# POWER_GEN.net
KiCad netlist of a schematic drawn in Altium Designer
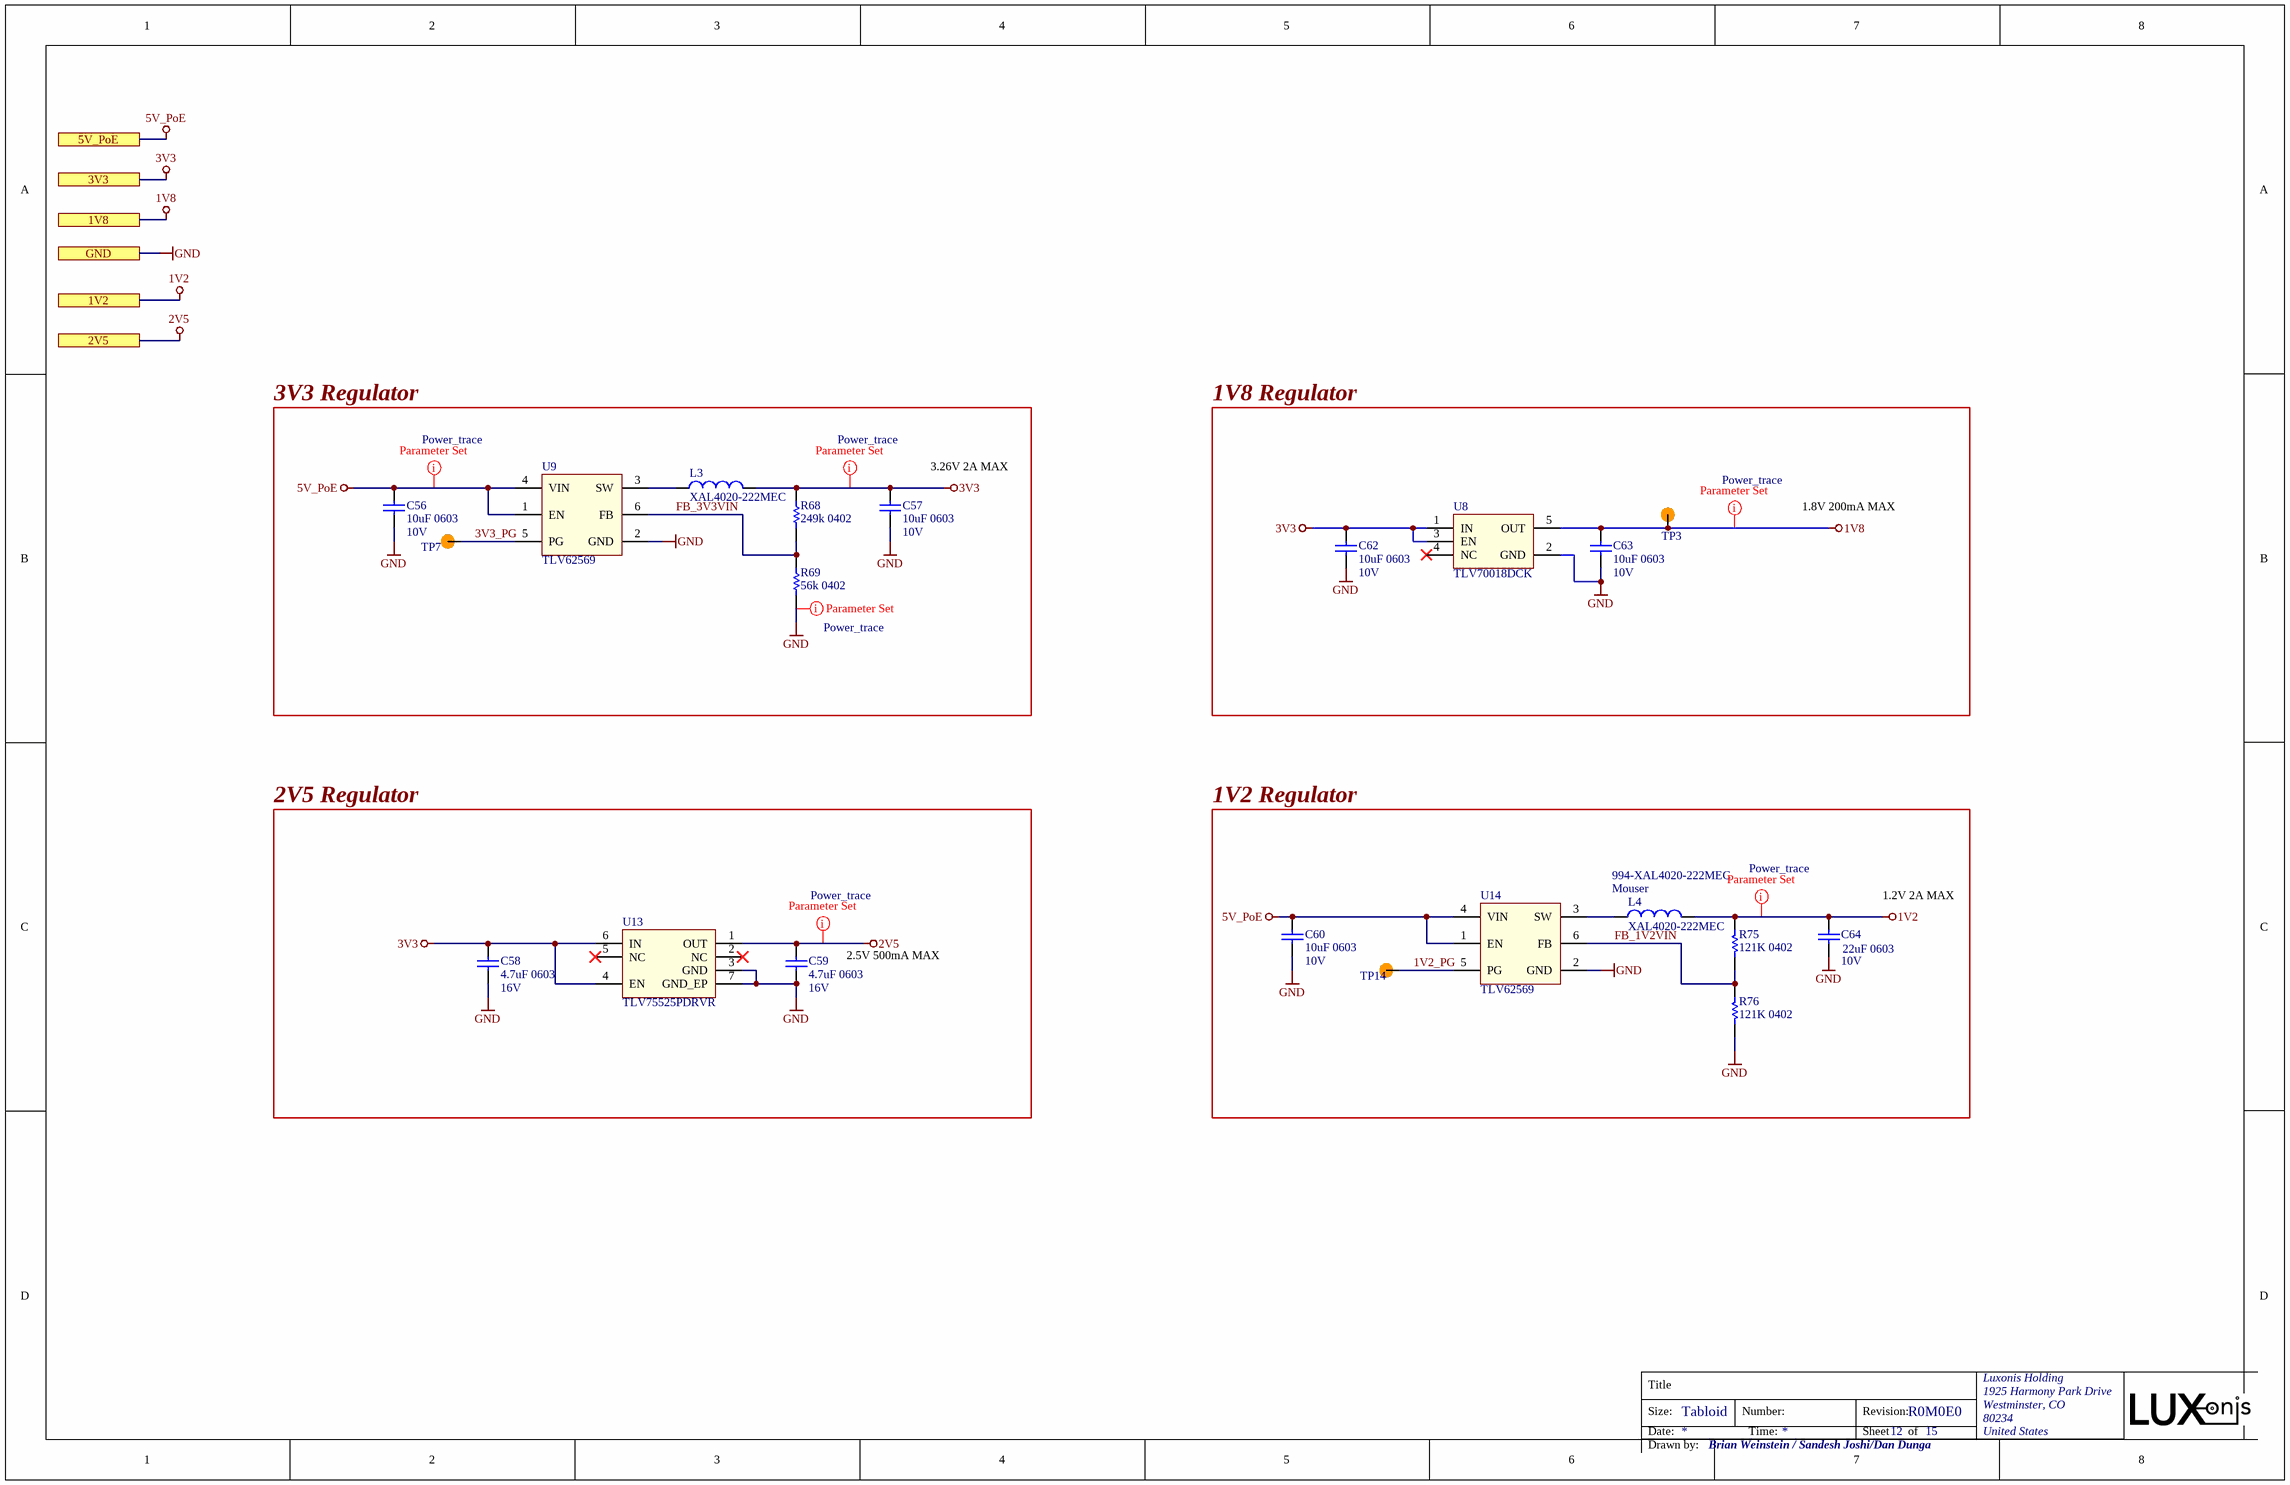
[diagram p0: POWER_GEN.SchDoc]

(export (version "E")
  (design (tool "Eeschema 10.0.6"))
  (components
    (comp (ref "C56")
      (value "10uF 0603")
      (footprint "CAP_Altium_Vault_Generic:CAPC0603(1608)100_N")
      (description "CAP CER 10UF 10V X5R 0603 20%")
      (fields (field (name "TOLERANCE") "20%") (field (name "VOLTAGE RATING") "10V"))
      (libsource (lib "OSHW_LuxonisMaster_20201223") (part "GRM188R61A106ME69D"))
    )
    (comp (ref "C57")
      (value "10uF 0603")
      (footprint "CAP_Altium_Vault_Generic:CAPC0603(1608)100_N")
      (description "CAP CER 10UF 10V X5R 0603 20%")
      (fields (field (name "TOLERANCE") "20%") (field (name "VOLTAGE RATING") "10V"))
      (libsource (lib "OSHW_LuxonisMaster_20201223") (part "GRM188R61A106ME69D"))
    )
    (comp (ref "C58")
      (value "4.7uF 0603")
      (footprint "CAPC0603(1608)100_N")
      (description "CAP CER 4.7UF 16V X5R 0603 10%")
      (fields (field (name "TOLERANCE") "10%") (field (name "VOLTAGE RATING") "16V"))
      (libsource (lib "LuxonisMaster") (part "GRM188R61C475KAAJD"))
    )
    (comp (ref "C59")
      (value "4.7uF 0603")
      (footprint "CAPC0603(1608)100_N")
      (description "CAP CER 4.7UF 16V X5R 0603 10%")
      (fields (field (name "TOLERANCE") "10%") (field (name "VOLTAGE RATING") "16V"))
      (libsource (lib "LuxonisMaster") (part "GRM188R61C475KAAJD"))
    )
    (comp (ref "C60")
      (value "10uF 0603")
      (footprint "CAP_Altium_Vault_Generic:CAPC0603(1608)100_N")
      (description "CAP CER 10UF 10V X5R 0603 20%")
      (fields (field (name "TOLERANCE") "20%") (field (name "VOLTAGE RATING") "10V"))
      (libsource (lib "OSHW_LuxonisMaster_20201223") (part "GRM188R61A106ME69D"))
    )
    (comp (ref "C62")
      (value "10uF 0603")
      (footprint "CAP_Altium_Vault_Generic:CAPC0603(1608)100_N")
      (description "CAP CER 10UF 10V X5R 0603 20%")
      (fields (field (name "TOLERANCE") "20%") (field (name "VOLTAGE RATING") "10V"))
      (libsource (lib "LuxonisMaster") (part "GRM188R61A106ME69D"))
    )
    (comp (ref "C63")
      (value "10uF 0603")
      (footprint "CAP_Altium_Vault_Generic:CAPC0603(1608)100_N")
      (description "CAP CER 10UF 10V X5R 0603 20%")
      (fields (field (name "TOLERANCE") "20%") (field (name "VOLTAGE RATING") "10V"))
      (libsource (lib "LuxonisMaster") (part "GRM188R61A106ME69D"))
    )
    (comp (ref "C64")
      (value "22uF 0603")
      (footprint "CAPC0603(1608)100_N")
      (description "CAP CER 22UF 10V X5R 0603 20%")
      (fields (field (name "TOLERANCE") "20%") (field (name "VOLTAGE RATING") "10V"))
      (libsource (lib "LuxonisMaster") (part "GRM188R61A226ME15D"))
    )
    (comp (ref "L3")
      (value "XAL4020-222MEC")
      (footprint "XAL4020")
      (description "INDUCTOR, 2.2UH, 5.5A,20%,52MHZ, REEL")
      (fields (field (name "TOLERANCE") "20%"))
      (libsource (lib "BW2098POE_Anfa") (part "XAL4020-222MEC"))
    )
    (comp (ref "L4")
      (value "XAL4020-222MEC")
      (footprint "XAL4020")
      (description "INDUCTOR, 2.2UH, 5.5A,20%,52MHZ, REEL")
      (fields
        (field (name "TOLERANCE") "20%")
        (field (name "SUPPLIER 1") "Mouser")
        (field (name "SUPPLIER PART NUMBER 1") "994-XAL4020-222MEC")
      )
      (libsource (lib "BW2098POE_Anfa") (part "XAL4020-222MEC"))
    )
    (comp (ref "R68")
      (value "249k 0402")
      (footprint "RESC0402(1005)_L")
      (description "RES SMD 249K OHM 1% 1/16W 0402")
      (fields (field (name "TOLERANCE") "1%"))
      (libsource (lib "OSHW_LuxonisMaster_20201223") (part "CRCW0402249KFKED"))
    )
    (comp (ref "R69")
      (value "56k 0402")
      (footprint "RESC0402(1005)_L")
      (description "VISHAY - CRCW040256K0FKED - RES, THICK FILM, 56K, 1%, 0.063W, 0402")
      (fields (field (name "TOLERANCE") "1%"))
      (libsource (lib "BW2098POE_Anfa") (part "CRCW040256K0FKED"))
    )
    (comp (ref "R75")
      (value "121K 0402")
      (footprint "RESC0402(1005)_N")
      (description "RES SMD 121K OHM 1% 1/16W 0402")
      (fields (field (name "TOLERANCE") "1%"))
      (libsource (lib "LuxonisMaster") (part "RC0402FR-07121KL"))
    )
    (comp (ref "R76")
      (value "121K 0402")
      (footprint "RESC0402(1005)_N")
      (description "RES SMD 121K OHM 1% 1/16W 0402")
      (fields (field (name "TOLERANCE") "1%"))
      (libsource (lib "LuxonisMaster") (part "RC0402FR-07121KL"))
    )
    (comp (ref "TP3")
      (value "TP100_200_NS")
      (footprint "TP100_200_NS")
      (libsource (lib "LuxonisMaster") (part "TEST_POINT"))
    )
    (comp (ref "TP7")
      (value "TP100_200_NS")
      (footprint "TP100_200_NS")
      (libsource (lib "LuxonisMaster") (part "TEST_POINT"))
    )
    (comp (ref "TP14")
      (value "TP100_200_NS")
      (footprint "TP100_200_NS")
      (libsource (lib "LuxonisMaster") (part "TEST_POINT"))
    )
    (comp (ref "U8")
      (value "TLV70018DCK")
      (footprint "TLV70018DCK")
      (description "IC REG LINEAR 1.8V 200MA SC70-5 Linear Voltage Regulator IC  1 Output  200mA SC-70-5")
      (libsource (lib "LuxonisMaster") (part "TLV70018DCK"))
    )
    (comp (ref "U9")
      (value "TLV62569")
      (footprint "SOT236")
      (description "2-A HIGH EFFICIENCY STEP-DOWN CO")
      (libsource (lib "BW2098POE_Anfa") (part "TLV62569PDDCT"))
    )
    (comp (ref "U13")
      (value "TLV75525PDRVR")
      (footprint "WSON-6")
      (description "500-mA, high-PSRR, low-IQ, low-dropout voltage regulator with enable 6-WSON -40 to 125")
      (libsource (lib "BW2098POE_Anfa") (part "TLV75525PDRVR"))
    )
    (comp (ref "U14")
      (value "TLV62569")
      (footprint "SOT236")
      (description "2-A HIGH EFFICIENCY STEP-DOWN CO")
      (libsource (lib "BW2098POE_Anfa") (part "TLV62569PDDCT"))
    )
  )
  (nets
    (net (code "1") (name "/1V2_PG") (class "Default")
      (node (ref "TP14") (pin "1") (pintype "passive"))
      (node (ref "U14") (pin "5") (pinfunction "PG_5") (pintype "passive"))
    )
    (net (code "2") (name "/3V3_PG") (class "Default")
      (node (ref "TP7") (pin "1") (pintype "passive"))
      (node (ref "U9") (pin "5") (pinfunction "PG_5") (pintype "passive"))
    )
    (net (code "3") (name "/FB_1V2VIN") (class "Default")
      (node (ref "R75") (pin "2") (pinfunction "2_2") (pintype "passive"))
      (node (ref "R76") (pin "1") (pinfunction "1_1") (pintype "passive"))
      (node (ref "U14") (pin "6") (pinfunction "FB_6") (pintype "passive"))
    )
    (net (code "4") (name "/FB_3V3VIN") (class "Default")
      (node (ref "R68") (pin "1") (pinfunction "1_1") (pintype "passive"))
      (node (ref "R69") (pin "2") (pinfunction "2_2") (pintype "passive"))
      (node (ref "U9") (pin "6") (pinfunction "FB_6") (pintype "passive"))
    )
    (net (code "5") (name "1V2") (class "Default")
      (node (ref "C64") (pin "2") (pinfunction "2_2") (pintype "passive"))
      (node (ref "L4") (pin "2") (pinfunction "2_2") (pintype "passive"))
      (node (ref "R75") (pin "1") (pinfunction "1_1") (pintype "passive"))
    )
    (net (code "6") (name "1V8") (class "Default")
      (node (ref "C63") (pin "2") (pinfunction "2_2") (pintype "passive"))
      (node (ref "TP3") (pin "1") (pintype "passive"))
      (node (ref "U8") (pin "5") (pinfunction "OUT_5") (pintype "passive"))
    )
    (net (code "7") (name "2V5") (class "Default")
      (node (ref "C59") (pin "2") (pinfunction "2_2") (pintype "passive"))
      (node (ref "U13") (pin "1") (pinfunction "OUT_1") (pintype "passive"))
    )
    (net (code "8") (name "3V3") (class "Default")
      (node (ref "C57") (pin "2") (pinfunction "2_2") (pintype "passive"))
      (node (ref "C58") (pin "2") (pinfunction "2_2") (pintype "passive"))
      (node (ref "C62") (pin "2") (pinfunction "2_2") (pintype "passive"))
      (node (ref "L3") (pin "2") (pinfunction "2_2") (pintype "passive"))
      (node (ref "R68") (pin "2") (pinfunction "2_2") (pintype "passive"))
      (node (ref "U13") (pin "4") (pinfunction "EN_4") (pintype "passive"))
      (node (ref "U13") (pin "6") (pinfunction "IN_6") (pintype "passive"))
      (node (ref "U8") (pin "1") (pinfunction "IN_1") (pintype "passive"))
      (node (ref "U8") (pin "3") (pinfunction "EN_3") (pintype "passive"))
    )
    (net (code "9") (name "5V_PoE") (class "Default")
      (node (ref "C56") (pin "2") (pinfunction "2_2") (pintype "passive"))
      (node (ref "C60") (pin "2") (pinfunction "2_2") (pintype "passive"))
      (node (ref "U14") (pin "1") (pinfunction "EN_1") (pintype "passive"))
      (node (ref "U14") (pin "4") (pinfunction "VIN_4") (pintype "passive"))
      (node (ref "U9") (pin "1") (pinfunction "EN_1") (pintype "passive"))
      (node (ref "U9") (pin "4") (pinfunction "VIN_4") (pintype "passive"))
    )
    (net (code "10") (name "GND") (class "Default")
      (node (ref "C56") (pin "1") (pinfunction "1_1") (pintype "passive"))
      (node (ref "C57") (pin "1") (pinfunction "1_1") (pintype "passive"))
      (node (ref "C58") (pin "1") (pinfunction "1_1") (pintype "passive"))
      (node (ref "C59") (pin "1") (pinfunction "1_1") (pintype "passive"))
      (node (ref "C60") (pin "1") (pinfunction "1_1") (pintype "passive"))
      (node (ref "C62") (pin "1") (pinfunction "1_1") (pintype "passive"))
      (node (ref "C63") (pin "1") (pinfunction "1_1") (pintype "passive"))
      (node (ref "C64") (pin "1") (pinfunction "1_1") (pintype "passive"))
      (node (ref "R69") (pin "1") (pinfunction "1_1") (pintype "passive"))
      (node (ref "R76") (pin "2") (pinfunction "2_2") (pintype "passive"))
      (node (ref "U13") (pin "3") (pinfunction "GND_3") (pintype "passive"))
      (node (ref "U13") (pin "7") (pinfunction "GND_EP_7") (pintype "passive"))
      (node (ref "U14") (pin "2") (pinfunction "GND_2") (pintype "passive"))
      (node (ref "U8") (pin "2") (pinfunction "GND_2") (pintype "passive"))
      (node (ref "U9") (pin "2") (pinfunction "GND_2") (pintype "passive"))
    )
    (net (code "11") (name "Net-(U9-SW)") (class "Default")
      (node (ref "L3") (pin "1") (pinfunction "1_1") (pintype "passive"))
      (node (ref "U9") (pin "3") (pinfunction "SW_3") (pintype "passive"))
    )
    (net (code "12") (name "Net-(U14-SW)") (class "Default")
      (node (ref "L4") (pin "1") (pinfunction "1_1") (pintype "passive"))
      (node (ref "U14") (pin "3") (pinfunction "SW_3") (pintype "passive"))
    )
    (net (code "13") (name "unconnected-(U8-NC-Pad4)") (class "Default")
      (node (ref "U8") (pin "4") (pinfunction "NC_4") (pintype "passive+no_connect"))
    )
    (net (code "14") (name "unconnected-(U13-NC-Pad2)") (class "Default")
      (node (ref "U13") (pin "2") (pinfunction "NC_2") (pintype "passive+no_connect"))
    )
    (net (code "15") (name "unconnected-(U13-NC-Pad5)") (class "Default")
      (node (ref "U13") (pin "5") (pinfunction "NC_5") (pintype "passive+no_connect"))
    )
  )
)
